# Sheet2.net
KiCad netlist of a schematic drawn in Altium Designer
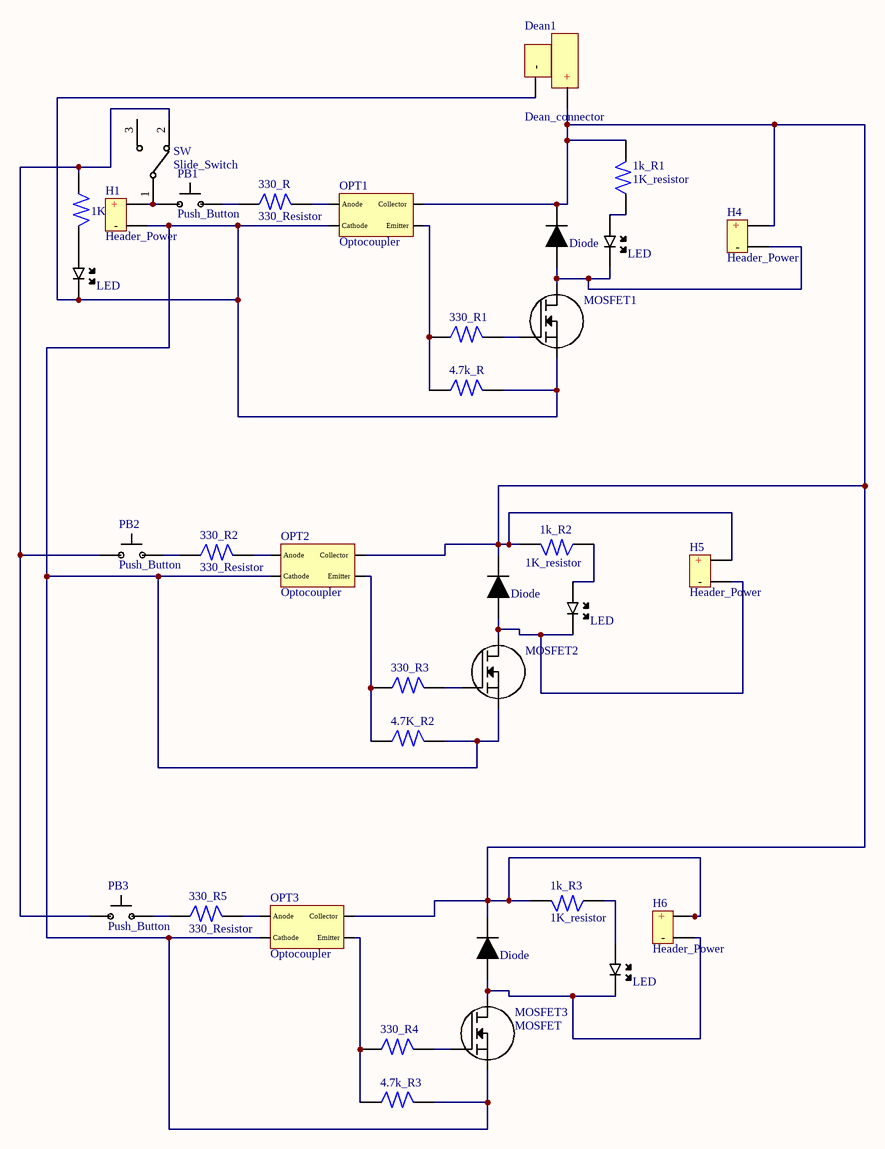
[diagram p0: Sheet2.SchDoc]

(export (version "E")
  (design (tool "Eeschema 10.0.6"))
  (components
    (comp (ref "1k_R1")
      (value "1K_resistor")
      (footprint "1k_resistor")
      (libsource (lib "Schlib1") (part "1K_resistor"))
    )
    (comp (ref "1k_R2")
      (value "1K_resistor")
      (footprint "1k_resistor")
      (libsource (lib "Schlib1") (part "1K_resistor"))
    )
    (comp (ref "1k_R3")
      (value "1K_resistor")
      (footprint "1k_resistor")
      (libsource (lib "Schlib1") (part "1K_resistor"))
    )
    (comp (ref "1k_RLED")
      (value "1K")
      (footprint "1k_resistor")
      (libsource (lib "Schlib1") (part "1K_resistor"))
    )
    (comp (ref "4.7k_R")
      (value "4.7k_Resistor")
      (footprint "4.7k_resistor")
      (libsource (lib "Schlib1") (part "4.7k_Resistor"))
    )
    (comp (ref "4.7K_R2")
      (value "4.7k_Resistor")
      (footprint "4.7k_resistor")
      (libsource (lib "Schlib1") (part "4.7k_Resistor"))
    )
    (comp (ref "4.7k_R3")
      (value "4.7k_Resistor")
      (footprint "4.7k_resistor")
      (libsource (lib "Schlib1") (part "4.7k_Resistor"))
    )
    (comp (ref "330_R")
      (value "330_Resistor")
      (footprint "330_resistor")
      (libsource (lib "Schlib1") (part "330_Resistor"))
    )
    (comp (ref "330_R1")
      (value "330_Resistor")
      (footprint "330_resistor")
      (libsource (lib "Schlib1") (part "330_Resistor"))
    )
    (comp (ref "330_R2")
      (value "330_Resistor")
      (footprint "330_resistor")
      (libsource (lib "Schlib1") (part "330_Resistor"))
    )
    (comp (ref "330_R3")
      (value "330_Resistor")
      (footprint "330_resistor")
      (libsource (lib "Schlib1") (part "330_Resistor"))
    )
    (comp (ref "330_R4")
      (value "330_Resistor")
      (footprint "330_resistor")
      (libsource (lib "Schlib1") (part "330_Resistor"))
    )
    (comp (ref "330_R5")
      (value "330_Resistor")
      (footprint "330_resistor")
      (libsource (lib "Schlib1") (part "330_Resistor"))
    )
    (comp (ref "D1") (value "Diode") (footprint "Diode") (libsource (lib "Schlib1") (part "Diode")))
    (comp (ref "D2") (value "Diode") (footprint "Diode") (libsource (lib "Schlib1") (part "Diode")))
    (comp (ref "D3") (value "Diode") (footprint "Diode") (libsource (lib "Schlib1") (part "Diode")))
    (comp (ref "Dean1")
      (value "Dean_connector")
      (footprint "Dean_connector")
      (libsource (lib "Schlib1") (part "Dean_connector"))
    )
    (comp (ref "H1")
      (value "Header_Power")
      (footprint "2_pinHeader")
      (libsource (lib "Schlib1") (part "Header_Power"))
    )
    (comp (ref "H4")
      (value "Header_Power")
      (footprint "2_pinHeader")
      (libsource (lib "Schlib1") (part "Header_Power"))
    )
    (comp (ref "H5")
      (value "Header_Power")
      (footprint "2_pinHeader")
      (libsource (lib "Schlib1") (part "Header_Power"))
    )
    (comp (ref "H6")
      (value "Header_Power")
      (footprint "2_pinHeader")
      (libsource (lib "Schlib1") (part "Header_Power"))
    )
    (comp (ref "LED1") (value "LED") (footprint "LED") (libsource (lib "Schlib1") (part "LED")))
    (comp (ref "LED2") (value "LED") (footprint "LED") (libsource (lib "Schlib1") (part "LED")))
    (comp (ref "LED3") (value "LED") (footprint "LED") (libsource (lib "Schlib1") (part "LED")))
    (comp (ref "LEDp") (value "LED") (footprint "LED") (libsource (lib "Schlib1") (part "LED")))
    (comp (ref "MOSFET1")
      (value "MOSFET")
      (footprint "MOSFET_IR540N")
      (libsource (lib "Schlib1") (part "MOSFET"))
    )
    (comp (ref "MOSFET2")
      (value "MOSFET")
      (footprint "MOSFET_IR540N")
      (libsource (lib "Schlib1") (part "MOSFET"))
    )
    (comp (ref "MOSFET3")
      (value "MOSFET")
      (footprint "MOSFET_IR540N")
      (libsource (lib "Schlib1") (part "MOSFET"))
    )
    (comp (ref "OPT1")
      (value "Optocoupler")
      (footprint "optocoupler")
      (libsource (lib "Schlib1") (part "Optocoupler"))
    )
    (comp (ref "OPT2")
      (value "Optocoupler")
      (footprint "optocoupler")
      (libsource (lib "Schlib1") (part "Optocoupler"))
    )
    (comp (ref "OPT3")
      (value "Optocoupler")
      (footprint "optocoupler")
      (libsource (lib "Schlib1") (part "Optocoupler"))
    )
    (comp (ref "PB1")
      (value "Push_Button")
      (footprint "push_button")
      (libsource (lib "Schlib1") (part "Push_Button"))
    )
    (comp (ref "PB2")
      (value "Push_Button")
      (footprint "push_button")
      (libsource (lib "Schlib1") (part "Push_Button"))
    )
    (comp (ref "PB3")
      (value "Push_Button")
      (footprint "push_button")
      (libsource (lib "Schlib1") (part "Push_Button"))
    )
    (comp (ref "SW")
      (value "Slide_Switch")
      (footprint "Slide_switch")
      (libsource (lib "Schlib1") (part "Slide_Switch"))
    )
  )
  (nets
    (net (code "1") (name "Net-(1k_RLED-Pad1)") (class "Default")
      (node (ref "1k_RLED") (pin "1") (pinfunction "1_1") (pintype "passive"))
      (node (ref "PB2") (pin "1") (pinfunction "1_1") (pintype "passive"))
      (node (ref "PB3") (pin "1") (pinfunction "1_1") (pintype "passive"))
      (node (ref "SW") (pin "2") (pinfunction "2_2") (pintype "passive"))
    )
    (net (code "2") (name "Net-(330_R-Pad1)") (class "Default")
      (node (ref "330_R") (pin "1") (pinfunction "1_1") (pintype "passive"))
      (node (ref "PB1") (pin "2") (pinfunction "2_2") (pintype "passive"))
    )
    (net (code "3") (name "Net-(330_R2-Pad1)") (class "Default")
      (node (ref "330_R2") (pin "1") (pinfunction "1_1") (pintype "passive"))
      (node (ref "PB2") (pin "2") (pinfunction "2_2") (pintype "passive"))
    )
    (net (code "4") (name "Net-(330_R5-Pad1)") (class "Default")
      (node (ref "330_R5") (pin "1") (pinfunction "1_1") (pintype "passive"))
      (node (ref "PB3") (pin "2") (pinfunction "2_2") (pintype "passive"))
    )
    (net (code "5") (name "Net-(D1-+)") (class "Default")
      (node (ref "D1") (pin "1") (pinfunction "+_1") (pintype "passive"))
      (node (ref "H4") (pin "2") (pinfunction "-_2") (pintype "passive"))
      (node (ref "LED1") (pin "1") (pinfunction "Anode_1") (pintype "passive"))
      (node (ref "MOSFET1") (pin "2") (pinfunction "Drain_2") (pintype "passive"))
    )
    (net (code "6") (name "Net-(D1--)") (class "Default")
      (node (ref "1k_R1") (pin "2") (pinfunction "2_2") (pintype "passive"))
      (node (ref "1k_R2") (pin "2") (pinfunction "2_2") (pintype "passive"))
      (node (ref "1k_R3") (pin "2") (pinfunction "2_2") (pintype "passive"))
      (node (ref "D1") (pin "2") (pinfunction "-_2") (pintype "passive"))
      (node (ref "D2") (pin "2") (pinfunction "-_2") (pintype "passive"))
      (node (ref "D3") (pin "2") (pinfunction "-_2") (pintype "passive"))
      (node (ref "Dean1") (pin "2") (pinfunction "+_2") (pintype "passive"))
      (node (ref "H4") (pin "1") (pinfunction "+_1") (pintype "passive"))
      (node (ref "H5") (pin "1") (pinfunction "+_1") (pintype "passive"))
      (node (ref "H6") (pin "1") (pinfunction "+_1") (pintype "passive"))
      (node (ref "OPT1") (pin "4") (pinfunction "Collector_4") (pintype "passive"))
      (node (ref "OPT2") (pin "4") (pinfunction "Collector_4") (pintype "passive"))
      (node (ref "OPT3") (pin "4") (pinfunction "Collector_4") (pintype "passive"))
    )
    (net (code "7") (name "Net-(D2-+)") (class "Default")
      (node (ref "D2") (pin "1") (pinfunction "+_1") (pintype "passive"))
      (node (ref "H5") (pin "2") (pinfunction "-_2") (pintype "passive"))
      (node (ref "LED2") (pin "1") (pinfunction "Anode_1") (pintype "passive"))
      (node (ref "MOSFET2") (pin "2") (pinfunction "Drain_2") (pintype "passive"))
    )
    (net (code "8") (name "Net-(D3-+)") (class "Default")
      (node (ref "D3") (pin "1") (pinfunction "+_1") (pintype "passive"))
      (node (ref "H6") (pin "2") (pinfunction "-_2") (pintype "passive"))
      (node (ref "LED3") (pin "1") (pinfunction "Anode_1") (pintype "passive"))
      (node (ref "MOSFET3") (pin "2") (pinfunction "Drain_2") (pintype "passive"))
    )
    (net (code "9") (name "Net-(Dean1--)") (class "Default")
      (node (ref "4.7K_R2") (pin "2") (pinfunction "2_2") (pintype "passive"))
      (node (ref "4.7k_R") (pin "2") (pinfunction "2_2") (pintype "passive"))
      (node (ref "4.7k_R3") (pin "2") (pinfunction "2_2") (pintype "passive"))
      (node (ref "Dean1") (pin "1") (pinfunction "-_1") (pintype "passive"))
      (node (ref "H1") (pin "2") (pinfunction "-_2") (pintype "passive"))
      (node (ref "LEDp") (pin "1") (pinfunction "Anode_1") (pintype "passive"))
      (node (ref "MOSFET1") (pin "3") (pinfunction "Source_3") (pintype "passive"))
      (node (ref "MOSFET2") (pin "3") (pinfunction "Source_3") (pintype "passive"))
      (node (ref "MOSFET3") (pin "3") (pinfunction "Source_3") (pintype "passive"))
      (node (ref "OPT1") (pin "2") (pinfunction "Cathode_2") (pintype "passive"))
      (node (ref "OPT2") (pin "2") (pinfunction "Cathode_2") (pintype "passive"))
      (node (ref "OPT3") (pin "2") (pinfunction "Cathode_2") (pintype "passive"))
    )
    (net (code "10") (name "Net-(H1-+)") (class "Default")
      (node (ref "H1") (pin "1") (pinfunction "+_1") (pintype "passive"))
      (node (ref "PB1") (pin "1") (pinfunction "1_1") (pintype "passive"))
      (node (ref "SW") (pin "1") (pinfunction "1_1") (pintype "passive"))
    )
    (net (code "11") (name "Net-(LED1-Cathode)") (class "Default")
      (node (ref "1k_R1") (pin "1") (pinfunction "1_1") (pintype "passive"))
      (node (ref "LED1") (pin "2") (pinfunction "Cathode_2") (pintype "passive"))
    )
    (net (code "12") (name "Net-(LED2-Cathode)") (class "Default")
      (node (ref "1k_R2") (pin "1") (pinfunction "1_1") (pintype "passive"))
      (node (ref "LED2") (pin "2") (pinfunction "Cathode_2") (pintype "passive"))
    )
    (net (code "13") (name "Net-(LED3-Cathode)") (class "Default")
      (node (ref "1k_R3") (pin "1") (pinfunction "1_1") (pintype "passive"))
      (node (ref "LED3") (pin "2") (pinfunction "Cathode_2") (pintype "passive"))
    )
    (net (code "14") (name "Net-(LEDp-Cathode)") (class "Default")
      (node (ref "1k_RLED") (pin "2") (pinfunction "2_2") (pintype "passive"))
      (node (ref "LEDp") (pin "2") (pinfunction "Cathode_2") (pintype "passive"))
    )
    (net (code "15") (name "Net-(MOSFET1-Gate)") (class "Default")
      (node (ref "330_R1") (pin "2") (pinfunction "2_2") (pintype "passive"))
      (node (ref "MOSFET1") (pin "1") (pinfunction "Gate_1") (pintype "passive"))
    )
    (net (code "16") (name "Net-(MOSFET2-Gate)") (class "Default")
      (node (ref "330_R3") (pin "2") (pinfunction "2_2") (pintype "passive"))
      (node (ref "MOSFET2") (pin "1") (pinfunction "Gate_1") (pintype "passive"))
    )
    (net (code "17") (name "Net-(MOSFET3-Gate)") (class "Default")
      (node (ref "330_R4") (pin "2") (pinfunction "2_2") (pintype "passive"))
      (node (ref "MOSFET3") (pin "1") (pinfunction "Gate_1") (pintype "passive"))
    )
    (net (code "18") (name "Net-(OPT1-Anode)") (class "Default")
      (node (ref "330_R") (pin "2") (pinfunction "2_2") (pintype "passive"))
      (node (ref "OPT1") (pin "1") (pinfunction "Anode_1") (pintype "passive"))
    )
    (net (code "19") (name "Net-(OPT1-Emitter)") (class "Default")
      (node (ref "330_R1") (pin "1") (pinfunction "1_1") (pintype "passive"))
      (node (ref "4.7k_R") (pin "1") (pinfunction "1_1") (pintype "passive"))
      (node (ref "OPT1") (pin "3") (pinfunction "Emitter_3") (pintype "passive"))
    )
    (net (code "20") (name "Net-(OPT2-Anode)") (class "Default")
      (node (ref "330_R2") (pin "2") (pinfunction "2_2") (pintype "passive"))
      (node (ref "OPT2") (pin "1") (pinfunction "Anode_1") (pintype "passive"))
    )
    (net (code "21") (name "Net-(OPT2-Emitter)") (class "Default")
      (node (ref "330_R3") (pin "1") (pinfunction "1_1") (pintype "passive"))
      (node (ref "4.7K_R2") (pin "1") (pinfunction "1_1") (pintype "passive"))
      (node (ref "OPT2") (pin "3") (pinfunction "Emitter_3") (pintype "passive"))
    )
    (net (code "22") (name "Net-(OPT3-Anode)") (class "Default")
      (node (ref "330_R5") (pin "2") (pinfunction "2_2") (pintype "passive"))
      (node (ref "OPT3") (pin "1") (pinfunction "Anode_1") (pintype "passive"))
    )
    (net (code "23") (name "Net-(OPT3-Emitter)") (class "Default")
      (node (ref "330_R4") (pin "1") (pinfunction "1_1") (pintype "passive"))
      (node (ref "4.7k_R3") (pin "1") (pinfunction "1_1") (pintype "passive"))
      (node (ref "OPT3") (pin "3") (pinfunction "Emitter_3") (pintype "passive"))
    )
    (net (code "24") (name "unconnected-(SW-Pad3)") (class "Default")
      (node (ref "SW") (pin "3") (pinfunction "3_3") (pintype "passive"))
    )
  )
)
